# 4_324_039__3_3.net
KiCad netlist of a schematic drawn in Altium Designer
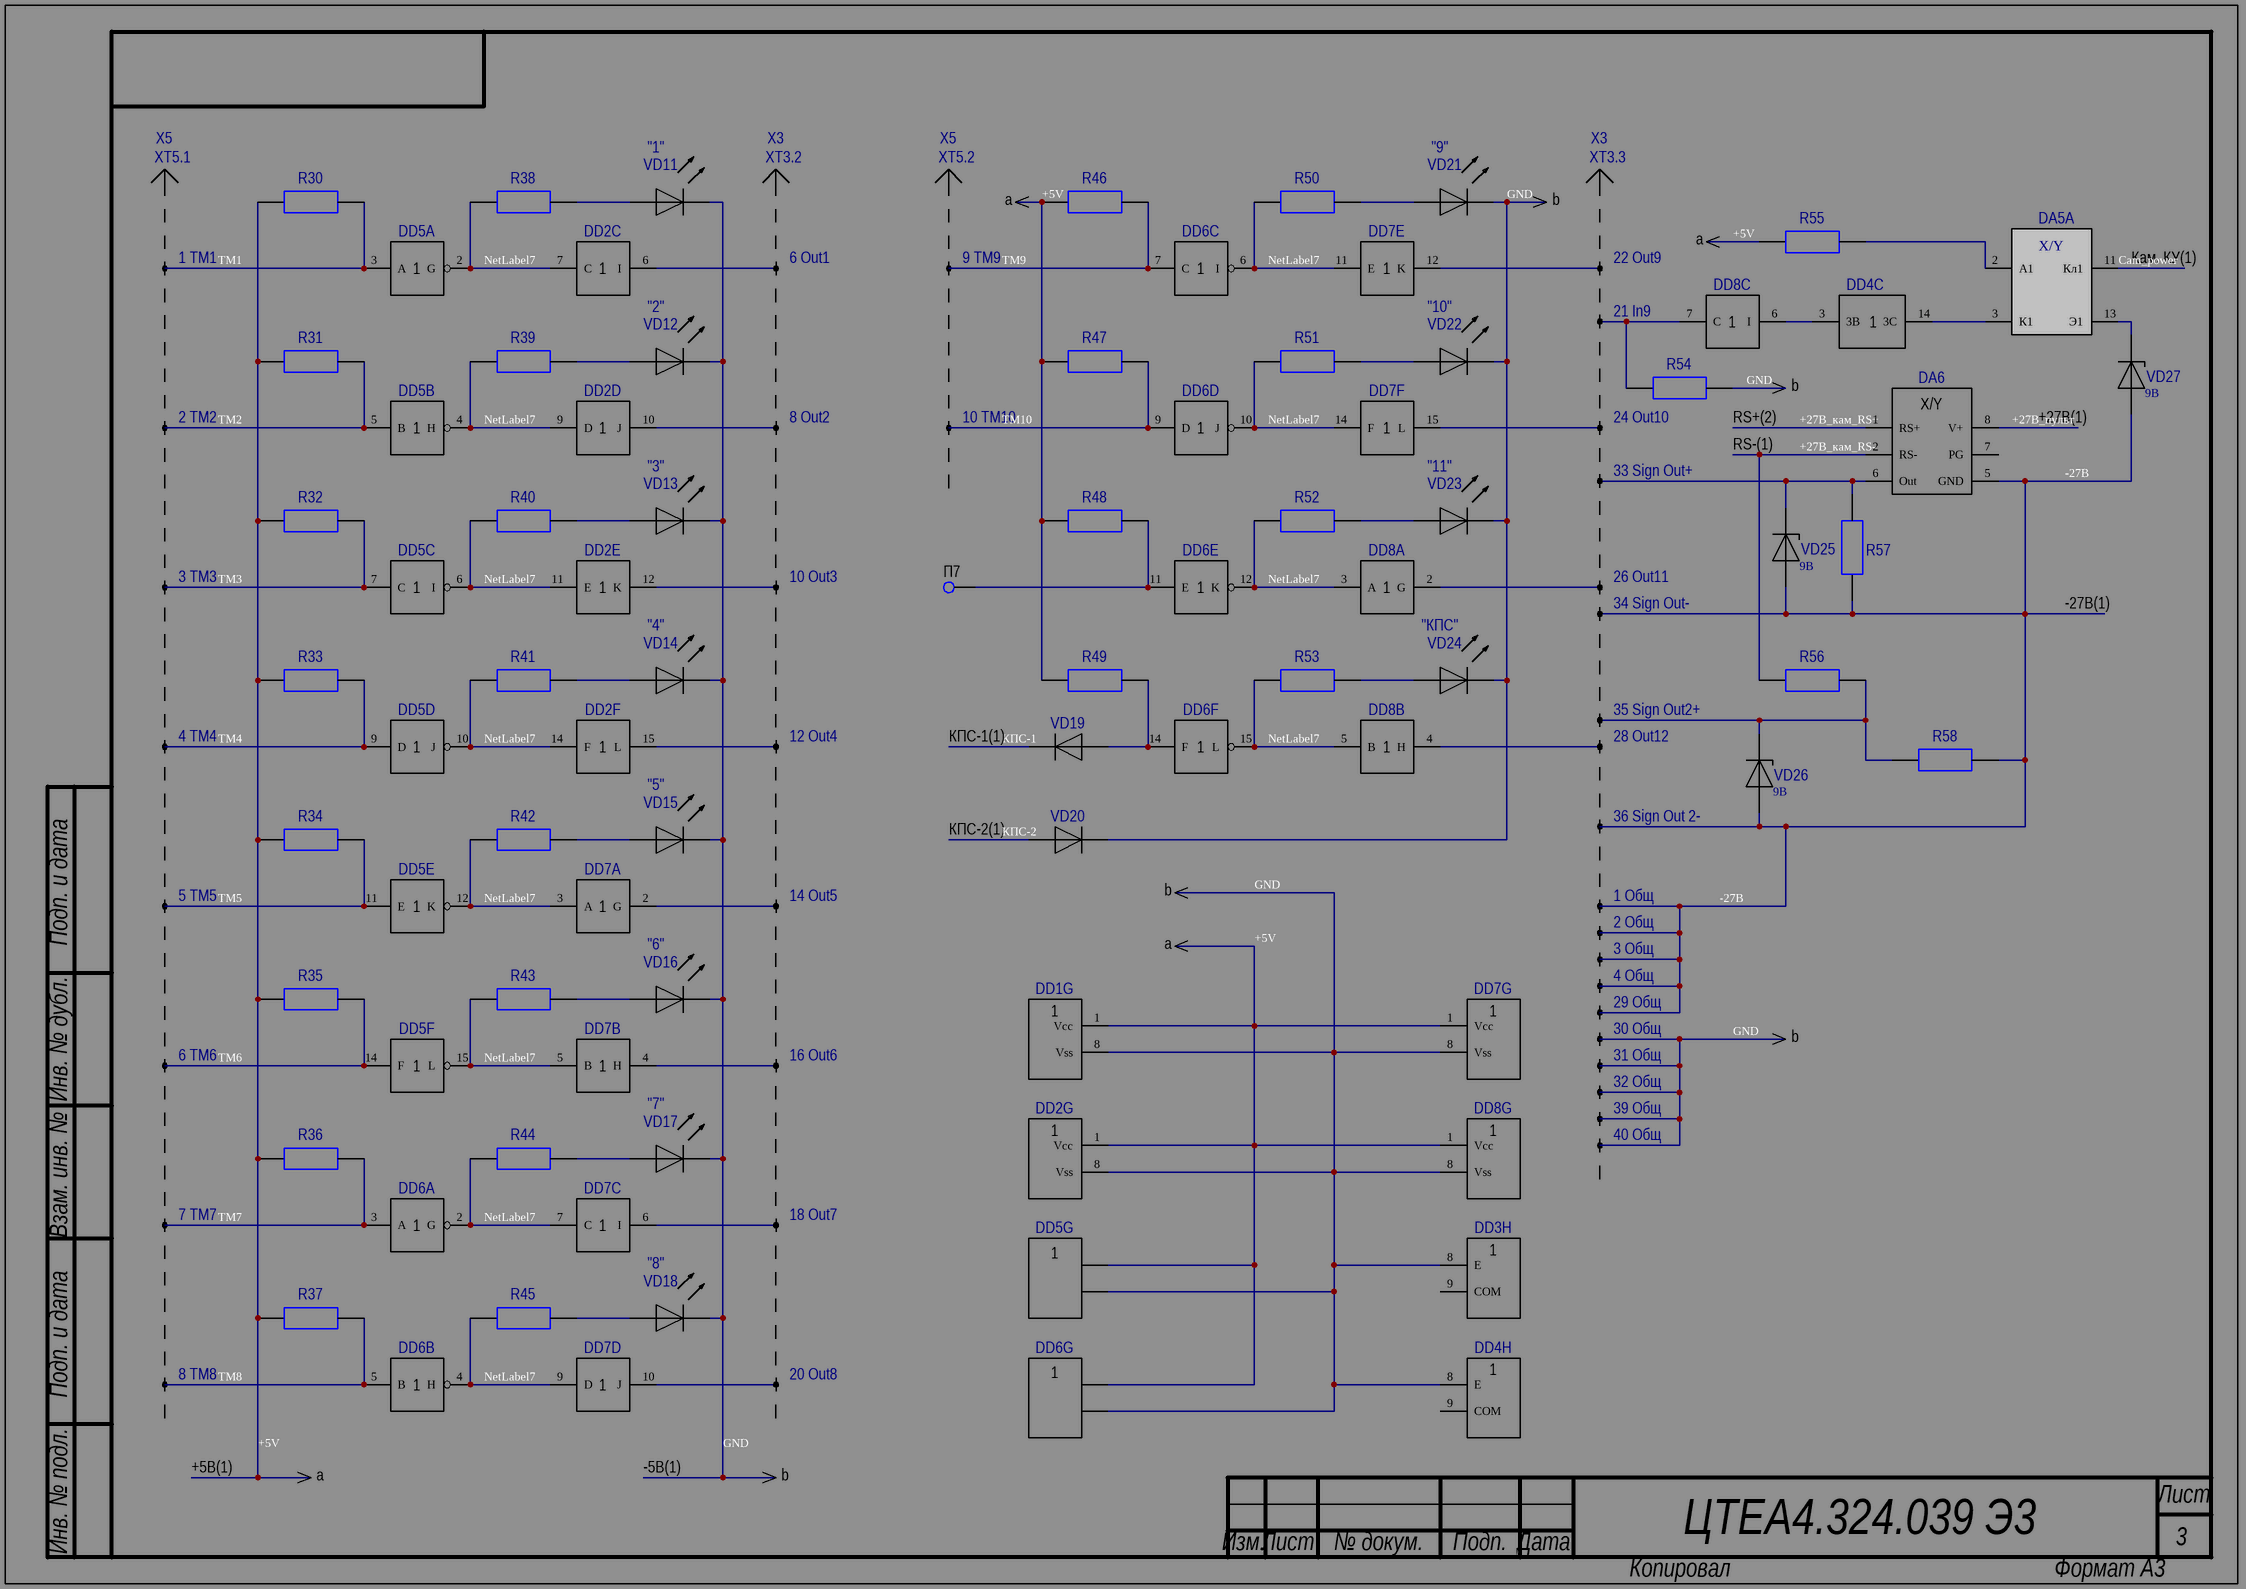
[diagram p0: ЦТЕА4.324.039_Э3_3.SchDoc]

(export (version "E")
  (design (tool "Eeschema 10.0.6"))
  (components
    (comp (ref "DA5")
      (value "249КП1С")
      (footprint "249KP1S_44_3208_125_12-3kl:249KP1S-44_3208_125_12")
      (libsource (lib "249KP1S_44_3208_125_12-3kl") (part "Microshema"))
    )
    (comp (ref "DA6")
      (value "MAX4172")
      (footprint "MAX4172")
      (libsource (lib "MAX4172-3kl") (part "MAX4172"))
    )
    (comp (ref "DD1")
      (value "Mikroshema")
      (footprint "CD4050BD")
      (description "CD4050BD")
      (libsource (lib "CD4050BD-3kl") (part "Mikroshema"))
    )
    (comp (ref "DD2")
      (value "Mikroshema")
      (footprint "CD4050BD")
      (description "CD4050BD")
      (libsource (lib "CD4050BD-3kl") (part "Mikroshema"))
    )
    (comp (ref "DD3")
      (value "Mikroshema")
      (footprint "UL2004AD")
      (description "ULN2004")
      (libsource (lib "ULN2004AD-3kl") (part "Mikroshema"))
    )
    (comp (ref "DD4")
      (value "Mikroshema")
      (footprint "UL2004AD")
      (description "ULN2004")
      (libsource (lib "ULN2004AD-3kl") (part "Mikroshema"))
    )
    (comp (ref "DD5")
      (value "Mikroshema")
      (footprint "CD4049UBD")
      (libsource (lib "CD4049UBD-3kl") (part "Mikroshema"))
    )
    (comp (ref "DD6")
      (value "Mikroshema")
      (footprint "CD4049UBD")
      (libsource (lib "CD4049UBD-3kl") (part "Mikroshema"))
    )
    (comp (ref "DD7")
      (value "Mikroshema")
      (footprint "CD4050BD")
      (description "CD4050BD")
      (libsource (lib "CD4050BD-3kl") (part "Mikroshema"))
    )
    (comp (ref "DD8")
      (value "Mikroshema")
      (footprint "CD4050BD")
      (description "CD4050BD")
      (libsource (lib "CD4050BD-3kl") (part "Mikroshema"))
    )
    (comp (ref "R30")
      (value "Res")
      (footprint "CR1206-JW-3301ELF")
      (libsource (lib "CR1206-JW-3301ELF-3kl") (part "Rezistor"))
    )
    (comp (ref "R31")
      (value "Res")
      (footprint "CR1206-JW-3301ELF")
      (libsource (lib "CR1206-JW-3301ELF-3kl") (part "Rezistor"))
    )
    (comp (ref "R32")
      (value "Res")
      (footprint "CR1206-JW-3301ELF")
      (libsource (lib "CR1206-JW-3301ELF-3kl") (part "Rezistor"))
    )
    (comp (ref "R33")
      (value "Res")
      (footprint "CR1206-JW-3301ELF")
      (libsource (lib "CR1206-JW-3301ELF-3kl") (part "Rezistor"))
    )
    (comp (ref "R34")
      (value "Res")
      (footprint "CR1206-JW-3301ELF")
      (libsource (lib "CR1206-JW-3301ELF-3kl") (part "Rezistor"))
    )
    (comp (ref "R35")
      (value "Res")
      (footprint "CR1206-JW-3301ELF")
      (libsource (lib "CR1206-JW-3301ELF-3kl") (part "Rezistor"))
    )
    (comp (ref "R36")
      (value "Res")
      (footprint "CR1206-JW-3301ELF")
      (libsource (lib "CR1206-JW-3301ELF-3kl") (part "Rezistor"))
    )
    (comp (ref "R37")
      (value "Res")
      (footprint "CR1206-JW-3301ELF")
      (libsource (lib "CR1206-JW-3301ELF-3kl") (part "Rezistor"))
    )
    (comp (ref "R38")
      (value "Res")
      (footprint "CR1206-JW-4700ELF")
      (libsource (lib "CR1206-JW-4700ELF-3kl") (part "Rezistor"))
    )
    (comp (ref "R39")
      (value "Res")
      (footprint "CR1206-JW-4700ELF")
      (libsource (lib "CR1206-JW-4700ELF-3kl") (part "Rezistor"))
    )
    (comp (ref "R40")
      (value "Res")
      (footprint "CR1206-JW-4700ELF")
      (libsource (lib "CR1206-JW-4700ELF-3kl") (part "Rezistor"))
    )
    (comp (ref "R41")
      (value "Res")
      (footprint "CR1206-JW-4700ELF")
      (libsource (lib "CR1206-JW-4700ELF-3kl") (part "Rezistor"))
    )
    (comp (ref "R42")
      (value "Res")
      (footprint "CR1206-JW-4700ELF")
      (libsource (lib "CR1206-JW-4700ELF-3kl") (part "Rezistor"))
    )
    (comp (ref "R43")
      (value "Res")
      (footprint "CR1206-JW-4700ELF")
      (libsource (lib "CR1206-JW-4700ELF-3kl") (part "Rezistor"))
    )
    (comp (ref "R44")
      (value "Res")
      (footprint "CR1206-JW-4700ELF")
      (libsource (lib "CR1206-JW-4700ELF-3kl") (part "Rezistor"))
    )
    (comp (ref "R45")
      (value "Res")
      (footprint "CR1206-JW-4700ELF")
      (libsource (lib "CR1206-JW-4700ELF-3kl") (part "Rezistor"))
    )
    (comp (ref "R46")
      (value "Res")
      (footprint "CR1206-JW-3301ELF")
      (libsource (lib "CR1206-JW-3301ELF-3kl") (part "Rezistor"))
    )
    (comp (ref "R47")
      (value "Res")
      (footprint "CR1206-JW-3301ELF")
      (libsource (lib "CR1206-JW-3301ELF-3kl") (part "Rezistor"))
    )
    (comp (ref "R48")
      (value "Res")
      (footprint "CR1206-JW-3301ELF")
      (libsource (lib "CR1206-JW-3301ELF-3kl") (part "Rezistor"))
    )
    (comp (ref "R49")
      (value "Res")
      (footprint "CR1206-JW-3301ELF")
      (libsource (lib "CR1206-JW-3301ELF-3kl") (part "Rezistor"))
    )
    (comp (ref "R50")
      (value "Res")
      (footprint "CR1206-JW-4700ELF")
      (libsource (lib "CR1206-JW-4700ELF-3kl") (part "Rezistor"))
    )
    (comp (ref "R51")
      (value "Res")
      (footprint "CR1206-JW-4700ELF")
      (libsource (lib "CR1206-JW-4700ELF-3kl") (part "Rezistor"))
    )
    (comp (ref "R52")
      (value "Res")
      (footprint "CR1206-JW-4700ELF")
      (libsource (lib "CR1206-JW-4700ELF-3kl") (part "Rezistor"))
    )
    (comp (ref "R53")
      (value "Res")
      (footprint "CR1206-JW-4700ELF")
      (libsource (lib "CR1206-JW-4700ELF-3kl") (part "Rezistor"))
    )
    (comp (ref "R54")
      (value "Res")
      (footprint "CR1206-JW-4701ELF")
      (libsource (lib "CR1206-JW-4701ELF-3kl") (part "Rezistor"))
    )
    (comp (ref "R55")
      (value "Res")
      (footprint "CR1206-JW-3300ELF")
      (libsource (lib "CR1206-JW-3300ELF-3kl") (part "Rezistor"))
    )
    (comp (ref "R56")
      (value "Res")
      (footprint "CR1206-JW-4701ELF")
      (libsource (lib "CR1206-JW-4701ELF-3kl") (part "Rezistor"))
    )
    (comp (ref "R57")
      (value "Res")
      (footprint "CR1206-JW-1001ELF")
      (libsource (lib "CR1206-JW-1001ELF-3kl") (part "Rezistor"))
    )
    (comp (ref "R58")
      (value "Res")
      (footprint "CR1206-JW-4700ELF")
      (libsource (lib "CR1206-JW-4700ELF-3kl") (part "Rezistor"))
    )
    (comp (ref "VD11")
      (value "\"1\"")
      (footprint "HLMP-D150")
      (libsource (lib "HLMP-D150-3kl") (part "Svetodiod"))
    )
    (comp (ref "VD12")
      (value "\"2\"")
      (footprint "HLMP-D150")
      (libsource (lib "HLMP-D150-3kl") (part "Svetodiod"))
    )
    (comp (ref "VD13")
      (value "\"3\"")
      (footprint "HLMP-D150")
      (libsource (lib "HLMP-D150-3kl") (part "Svetodiod"))
    )
    (comp (ref "VD14")
      (value "\"4\"")
      (footprint "HLMP-D150")
      (libsource (lib "HLMP-D150-3kl") (part "Svetodiod"))
    )
    (comp (ref "VD15")
      (value "\"5\"")
      (footprint "HLMP-D150")
      (libsource (lib "HLMP-D150-3kl") (part "Svetodiod"))
    )
    (comp (ref "VD16")
      (value "\"6\"")
      (footprint "HLMP-D150")
      (libsource (lib "HLMP-D150-3kl") (part "Svetodiod"))
    )
    (comp (ref "VD17")
      (value "\"7\"")
      (footprint "HLMP-D150")
      (libsource (lib "HLMP-D150-3kl") (part "Svetodiod"))
    )
    (comp (ref "VD18")
      (value "\"8\"")
      (footprint "HLMP-D150")
      (libsource (lib "HLMP-D150-3kl") (part "Svetodiod"))
    )
    (comp (ref "VD19")
      (value "Schottky")
      (footprint "10MQ060N")
      (libsource (lib "10MQ060N-3kl") (part "Diod"))
    )
    (comp (ref "VD20")
      (value "Schottky")
      (footprint "10MQ060N")
      (libsource (lib "10MQ060N-3kl") (part "Diod"))
    )
    (comp (ref "VD21")
      (value "\"9\"")
      (footprint "HLMP-D150")
      (libsource (lib "HLMP-D150-3kl") (part "Svetodiod"))
    )
    (comp (ref "VD22")
      (value "\"10\"")
      (footprint "HLMP-D150")
      (libsource (lib "HLMP-D150-3kl") (part "Svetodiod"))
    )
    (comp (ref "VD23")
      (value "\"11\"")
      (footprint "HLMP-D150")
      (libsource (lib "HLMP-D150-3kl") (part "Svetodiod"))
    )
    (comp (ref "VD24")
      (value "\"КПС\"")
      (footprint "HLMP-D150")
      (libsource (lib "HLMP-D150-3kl") (part "Svetodiod"))
    )
    (comp (ref "VD25")
      (value "9В")
      (footprint "1N4754A-25_0000_145_18")
      (description "zener")
      (libsource (lib "1N4754A-f1-3kl") (part "Diod"))
    )
    (comp (ref "VD26")
      (value "9В")
      (footprint "1N4754A-25_0000_145_18")
      (description "zener")
      (libsource (lib "1N4754A-f1-3kl") (part "Diod"))
    )
    (comp (ref "VD27")
      (value "9В")
      (footprint "1N4754A-25_0000_145_18")
      (description "zener")
      (libsource (lib "1N4754A-f1-3kl") (part "Diod"))
    )
    (comp (ref "XT3")
      (value "1 Общ")
      (footprint "PLD-40")
      (libsource (lib "PLD-40-3kl") (part "Razem shtyrevoj"))
    )
    (comp (ref "XT5")
      (value "1 ТМ1")
      (footprint "PLD-16")
      (description "PLD16")
      (libsource (lib "PLD-16-3kl") (part "Razem shtyrevoj"))
    )
    (comp (ref "П7")
      (value "~")
      (footprint "Pad")
      (description "pad")
      (libsource (lib "Pad-3kl") (part "Pad"))
    )
  )
  (nets
    (net (code "1") (name "/+5V") (class "Default")
      (node (ref "DD1") (pin "1") (pinfunction "Vcc_1") (pintype "power_in"))
      (node (ref "DD2") (pin "1") (pinfunction "Vcc_1") (pintype "power_in"))
      (node (ref "DD5") (pin "1") (pinfunction "Vcc_1") (pintype "power_in"))
      (node (ref "DD6") (pin "1") (pinfunction "Vcc_1") (pintype "power_in"))
      (node (ref "DD7") (pin "1") (pinfunction "Vcc_1") (pintype "power_in"))
      (node (ref "DD8") (pin "1") (pinfunction "Vcc_1") (pintype "power_in"))
      (node (ref "R30") (pin "1") (pinfunction "1_1") (pintype "passive"))
      (node (ref "R31") (pin "1") (pinfunction "1_1") (pintype "passive"))
      (node (ref "R32") (pin "1") (pinfunction "1_1") (pintype "passive"))
      (node (ref "R33") (pin "1") (pinfunction "1_1") (pintype "passive"))
      (node (ref "R34") (pin "1") (pinfunction "1_1") (pintype "passive"))
      (node (ref "R35") (pin "1") (pinfunction "1_1") (pintype "passive"))
      (node (ref "R36") (pin "1") (pinfunction "1_1") (pintype "passive"))
      (node (ref "R37") (pin "1") (pinfunction "1_1") (pintype "passive"))
      (node (ref "R46") (pin "1") (pinfunction "1_1") (pintype "passive"))
      (node (ref "R47") (pin "1") (pinfunction "1_1") (pintype "passive"))
      (node (ref "R48") (pin "1") (pinfunction "1_1") (pintype "passive"))
      (node (ref "R49") (pin "1") (pinfunction "1_1") (pintype "passive"))
      (node (ref "R55") (pin "1") (pinfunction "1_1") (pintype "passive"))
    )
    (net (code "2") (name "/+27В_кам_RS+") (class "Default")
      (node (ref "DA6") (pin "1") (pinfunction "RS+_1") (pintype "passive"))
    )
    (net (code "3") (name "/+27В_кам_RS-") (class "Default")
      (node (ref "DA6") (pin "2") (pinfunction "RS-_2") (pintype "passive"))
      (node (ref "R56") (pin "1") (pinfunction "1_1") (pintype "passive"))
    )
    (net (code "4") (name "/+27В_пульт") (class "Default")
      (node (ref "DA6") (pin "8") (pinfunction "V+_8") (pintype "passive"))
    )
    (net (code "5") (name "/-27В") (class "Default")
      (node (ref "DA6") (pin "5") (pinfunction "GND_5") (pintype "passive"))
      (node (ref "R57") (pin "1") (pinfunction "1_1") (pintype "passive"))
      (node (ref "R58") (pin "2") (pinfunction "2_2") (pintype "passive"))
      (node (ref "VD25") (pin "1") (pinfunction "A_1") (pintype "passive"))
      (node (ref "VD26") (pin "1") (pinfunction "A_1") (pintype "passive"))
      (node (ref "VD27") (pin "1") (pinfunction "A_1") (pintype "passive"))
      (node (ref "XT3") (pin "1") (pinfunction "1_1") (pintype "passive"))
      (node (ref "XT3") (pin "2") (pinfunction "2_2") (pintype "passive"))
      (node (ref "XT3") (pin "29") (pinfunction "29_29") (pintype "passive"))
      (node (ref "XT3") (pin "3") (pinfunction "3_3") (pintype "passive"))
      (node (ref "XT3") (pin "34") (pinfunction "34_34") (pintype "passive"))
      (node (ref "XT3") (pin "36") (pinfunction "36_36") (pintype "passive"))
      (node (ref "XT3") (pin "4") (pinfunction "4_4") (pintype "passive"))
    )
    (net (code "6") (name "/Cam_power") (class "Default")
      (node (ref "DA5") (pin "11") (pinfunction "Кл1_11") (pintype "passive"))
    )
    (net (code "7") (name "/GND") (class "Default")
      (node (ref "DD1") (pin "8") (pinfunction "Vss_8") (pintype "power_in"))
      (node (ref "DD2") (pin "8") (pinfunction "Vss_8") (pintype "power_in"))
      (node (ref "DD3") (pin "8") (pinfunction "E_8") (pintype "power_in"))
      (node (ref "DD4") (pin "8") (pinfunction "E_8") (pintype "power_in"))
      (node (ref "DD5") (pin "8") (pinfunction "Vss_8") (pintype "power_in"))
      (node (ref "DD6") (pin "8") (pinfunction "Vss_8") (pintype "power_in"))
      (node (ref "DD7") (pin "8") (pinfunction "Vss_8") (pintype "power_in"))
      (node (ref "DD8") (pin "8") (pinfunction "Vss_8") (pintype "power_in"))
      (node (ref "R54") (pin "2") (pinfunction "2_2") (pintype "passive"))
      (node (ref "VD11") (pin "2") (pinfunction "C_2") (pintype "passive"))
      (node (ref "VD12") (pin "2") (pinfunction "C_2") (pintype "passive"))
      (node (ref "VD13") (pin "2") (pinfunction "C_2") (pintype "passive"))
      (node (ref "VD14") (pin "2") (pinfunction "C_2") (pintype "passive"))
      (node (ref "VD15") (pin "2") (pinfunction "C_2") (pintype "passive"))
      (node (ref "VD16") (pin "2") (pinfunction "C_2") (pintype "passive"))
      (node (ref "VD17") (pin "2") (pinfunction "C_2") (pintype "passive"))
      (node (ref "VD18") (pin "2") (pinfunction "C_2") (pintype "passive"))
      (node (ref "VD20") (pin "2") (pinfunction "C_2") (pintype "passive"))
      (node (ref "VD21") (pin "2") (pinfunction "C_2") (pintype "passive"))
      (node (ref "VD22") (pin "2") (pinfunction "C_2") (pintype "passive"))
      (node (ref "VD23") (pin "2") (pinfunction "C_2") (pintype "passive"))
      (node (ref "VD24") (pin "2") (pinfunction "C_2") (pintype "passive"))
      (node (ref "XT3") (pin "30") (pinfunction "30_30") (pintype "passive"))
      (node (ref "XT3") (pin "31") (pinfunction "31_31") (pintype "passive"))
      (node (ref "XT3") (pin "32") (pinfunction "32_32") (pintype "passive"))
      (node (ref "XT3") (pin "39") (pinfunction "39_39") (pintype "passive"))
      (node (ref "XT3") (pin "40") (pinfunction "40_40") (pintype "passive"))
    )
    (net (code "8") (name "/NetLabel7") (class "Default")
      (node (ref "DD2") (pin "11") (pinfunction "E_11") (pintype "passive"))
      (node (ref "DD2") (pin "14") (pinfunction "F_14") (pintype "passive"))
      (node (ref "DD2") (pin "7") (pinfunction "C_7") (pintype "passive"))
      (node (ref "DD2") (pin "9") (pinfunction "D_9") (pintype "passive"))
      (node (ref "DD5") (pin "10") (pinfunction "J_10") (pintype "passive"))
      (node (ref "DD5") (pin "12") (pinfunction "K_12") (pintype "passive"))
      (node (ref "DD5") (pin "15") (pinfunction "L_15") (pintype "passive"))
      (node (ref "DD5") (pin "2") (pinfunction "G_2") (pintype "passive"))
      (node (ref "DD5") (pin "4") (pinfunction "H_4") (pintype "passive"))
      (node (ref "DD5") (pin "6") (pinfunction "I_6") (pintype "passive"))
      (node (ref "DD6") (pin "10") (pinfunction "J_10") (pintype "passive"))
      (node (ref "DD6") (pin "12") (pinfunction "K_12") (pintype "passive"))
      (node (ref "DD6") (pin "15") (pinfunction "L_15") (pintype "passive"))
      (node (ref "DD6") (pin "2") (pinfunction "G_2") (pintype "passive"))
      (node (ref "DD6") (pin "4") (pinfunction "H_4") (pintype "passive"))
      (node (ref "DD6") (pin "6") (pinfunction "I_6") (pintype "passive"))
      (node (ref "DD7") (pin "11") (pinfunction "E_11") (pintype "passive"))
      (node (ref "DD7") (pin "14") (pinfunction "F_14") (pintype "passive"))
      (node (ref "DD7") (pin "3") (pinfunction "A_3") (pintype "passive"))
      (node (ref "DD7") (pin "5") (pinfunction "B_5") (pintype "passive"))
      (node (ref "DD7") (pin "7") (pinfunction "C_7") (pintype "passive"))
      (node (ref "DD7") (pin "9") (pinfunction "D_9") (pintype "passive"))
      (node (ref "DD8") (pin "3") (pinfunction "A_3") (pintype "passive"))
      (node (ref "DD8") (pin "5") (pinfunction "B_5") (pintype "passive"))
      (node (ref "R38") (pin "1") (pinfunction "1_1") (pintype "passive"))
      (node (ref "R39") (pin "1") (pinfunction "1_1") (pintype "passive"))
      (node (ref "R40") (pin "1") (pinfunction "1_1") (pintype "passive"))
      (node (ref "R41") (pin "1") (pinfunction "1_1") (pintype "passive"))
      (node (ref "R42") (pin "1") (pinfunction "1_1") (pintype "passive"))
      (node (ref "R43") (pin "1") (pinfunction "1_1") (pintype "passive"))
      (node (ref "R44") (pin "1") (pinfunction "1_1") (pintype "passive"))
      (node (ref "R45") (pin "1") (pinfunction "1_1") (pintype "passive"))
      (node (ref "R50") (pin "1") (pinfunction "1_1") (pintype "passive"))
      (node (ref "R51") (pin "1") (pinfunction "1_1") (pintype "passive"))
      (node (ref "R52") (pin "1") (pinfunction "1_1") (pintype "passive"))
      (node (ref "R53") (pin "1") (pinfunction "1_1") (pintype "passive"))
    )
    (net (code "9") (name "/КПС-1") (class "Default")
      (node (ref "VD19") (pin "2") (pinfunction "C_2") (pintype "passive"))
    )
    (net (code "10") (name "/КПС-2") (class "Default")
      (node (ref "VD20") (pin "1") (pinfunction "A_1") (pintype "passive"))
    )
    (net (code "11") (name "/ТМ1") (class "Default")
      (node (ref "DD5") (pin "3") (pinfunction "A_3") (pintype "passive"))
      (node (ref "R30") (pin "2") (pinfunction "2_2") (pintype "passive"))
      (node (ref "XT5") (pin "1") (pinfunction "1_1") (pintype "passive"))
    )
    (net (code "12") (name "/ТМ2") (class "Default")
      (node (ref "DD5") (pin "5") (pinfunction "B_5") (pintype "passive"))
      (node (ref "R31") (pin "2") (pinfunction "2_2") (pintype "passive"))
      (node (ref "XT5") (pin "2") (pinfunction "2_2") (pintype "passive"))
    )
    (net (code "13") (name "/ТМ3") (class "Default")
      (node (ref "DD5") (pin "7") (pinfunction "C_7") (pintype "passive"))
      (node (ref "R32") (pin "2") (pinfunction "2_2") (pintype "passive"))
      (node (ref "XT5") (pin "3") (pinfunction "3_3") (pintype "passive"))
    )
    (net (code "14") (name "/ТМ4") (class "Default")
      (node (ref "DD5") (pin "9") (pinfunction "D_9") (pintype "passive"))
      (node (ref "R33") (pin "2") (pinfunction "2_2") (pintype "passive"))
      (node (ref "XT5") (pin "4") (pinfunction "4_4") (pintype "passive"))
    )
    (net (code "15") (name "/ТМ5") (class "Default")
      (node (ref "DD5") (pin "11") (pinfunction "E_11") (pintype "passive"))
      (node (ref "R34") (pin "2") (pinfunction "2_2") (pintype "passive"))
      (node (ref "XT5") (pin "5") (pinfunction "5_5") (pintype "passive"))
    )
    (net (code "16") (name "/ТМ6") (class "Default")
      (node (ref "DD5") (pin "14") (pinfunction "F_14") (pintype "passive"))
      (node (ref "R35") (pin "2") (pinfunction "2_2") (pintype "passive"))
      (node (ref "XT5") (pin "6") (pinfunction "6_6") (pintype "passive"))
    )
    (net (code "17") (name "/ТМ7") (class "Default")
      (node (ref "DD6") (pin "3") (pinfunction "A_3") (pintype "passive"))
      (node (ref "R36") (pin "2") (pinfunction "2_2") (pintype "passive"))
      (node (ref "XT5") (pin "7") (pinfunction "7_7") (pintype "passive"))
    )
    (net (code "18") (name "/ТМ8") (class "Default")
      (node (ref "DD6") (pin "5") (pinfunction "B_5") (pintype "passive"))
      (node (ref "R37") (pin "2") (pinfunction "2_2") (pintype "passive"))
      (node (ref "XT5") (pin "8") (pinfunction "8_8") (pintype "passive"))
    )
    (net (code "19") (name "/ТМ9") (class "Default")
      (node (ref "DD6") (pin "7") (pinfunction "C_7") (pintype "passive"))
      (node (ref "R46") (pin "2") (pinfunction "2_2") (pintype "passive"))
      (node (ref "XT5") (pin "9") (pinfunction "9_9") (pintype "passive"))
    )
    (net (code "20") (name "/ТМ10") (class "Default")
      (node (ref "DD6") (pin "9") (pinfunction "D_9") (pintype "passive"))
      (node (ref "R47") (pin "2") (pinfunction "2_2") (pintype "passive"))
      (node (ref "XT5") (pin "10") (pinfunction "10_10") (pintype "passive"))
    )
    (net (code "21") (name "Net-(DA5A-А1)") (class "Default")
      (node (ref "DA5") (pin "2") (pinfunction "А1_2") (pintype "passive"))
      (node (ref "R55") (pin "2") (pinfunction "2_2") (pintype "passive"))
    )
    (net (code "22") (name "Net-(DA5A-К1)") (class "Default")
      (node (ref "DA5") (pin "3") (pinfunction "К1_3") (pintype "passive"))
      (node (ref "DD4") (pin "14") (pinfunction "3C_14") (pintype "passive"))
    )
    (net (code "23") (name "Net-(DA5A-Э1)") (class "Default")
      (node (ref "DA5") (pin "13") (pinfunction "Э1_13") (pintype "passive"))
      (node (ref "VD27") (pin "2") (pinfunction "C_2") (pintype "passive"))
    )
    (net (code "24") (name "Net-(DA6-Out)") (class "Default")
      (node (ref "DA6") (pin "6") (pinfunction "Out_6") (pintype "passive"))
      (node (ref "R57") (pin "2") (pinfunction "2_2") (pintype "passive"))
      (node (ref "VD25") (pin "2") (pinfunction "C_2") (pintype "passive"))
      (node (ref "XT3") (pin "33") (pinfunction "33_33") (pintype "passive"))
    )
    (net (code "25") (name "Net-(DD2C-I)") (class "Default")
      (node (ref "DD2") (pin "6") (pinfunction "I_6") (pintype "passive"))
      (node (ref "XT3") (pin "6") (pinfunction "6_6") (pintype "passive"))
    )
    (net (code "26") (name "Net-(DD2D-J)") (class "Default")
      (node (ref "DD2") (pin "10") (pinfunction "J_10") (pintype "passive"))
      (node (ref "XT3") (pin "8") (pinfunction "8_8") (pintype "passive"))
    )
    (net (code "27") (name "Net-(DD2E-K)") (class "Default")
      (node (ref "DD2") (pin "12") (pinfunction "K_12") (pintype "passive"))
      (node (ref "XT3") (pin "10") (pinfunction "10_10") (pintype "passive"))
    )
    (net (code "28") (name "Net-(DD2F-L)") (class "Default")
      (node (ref "DD2") (pin "15") (pinfunction "L_15") (pintype "passive"))
      (node (ref "XT3") (pin "12") (pinfunction "12_12") (pintype "passive"))
    )
    (net (code "29") (name "Net-(DD4C-3B)") (class "Default")
      (node (ref "DD4") (pin "3") (pinfunction "3B_3") (pintype "passive"))
      (node (ref "DD8") (pin "6") (pinfunction "I_6") (pintype "passive"))
    )
    (net (code "30") (name "Net-(DD6E-E)") (class "Default")
      (node (ref "DD6") (pin "11") (pinfunction "E_11") (pintype "passive"))
      (node (ref "R48") (pin "2") (pinfunction "2_2") (pintype "passive"))
      (node (ref "П7") (pin "1") (pinfunction "1_1") (pintype "passive"))
    )
    (net (code "31") (name "Net-(DD6F-F)") (class "Default")
      (node (ref "DD6") (pin "14") (pinfunction "F_14") (pintype "passive"))
      (node (ref "R49") (pin "2") (pinfunction "2_2") (pintype "passive"))
      (node (ref "VD19") (pin "1") (pinfunction "A_1") (pintype "passive"))
    )
    (net (code "32") (name "Net-(DD7A-G)") (class "Default")
      (node (ref "DD7") (pin "2") (pinfunction "G_2") (pintype "passive"))
      (node (ref "XT3") (pin "14") (pinfunction "14_14") (pintype "passive"))
    )
    (net (code "33") (name "Net-(DD7B-H)") (class "Default")
      (node (ref "DD7") (pin "4") (pinfunction "H_4") (pintype "passive"))
      (node (ref "XT3") (pin "16") (pinfunction "16_16") (pintype "passive"))
    )
    (net (code "34") (name "Net-(DD7C-I)") (class "Default")
      (node (ref "DD7") (pin "6") (pinfunction "I_6") (pintype "passive"))
      (node (ref "XT3") (pin "18") (pinfunction "18_18") (pintype "passive"))
    )
    (net (code "35") (name "Net-(DD7D-J)") (class "Default")
      (node (ref "DD7") (pin "10") (pinfunction "J_10") (pintype "passive"))
      (node (ref "XT3") (pin "20") (pinfunction "20_20") (pintype "passive"))
    )
    (net (code "36") (name "Net-(DD7E-K)") (class "Default")
      (node (ref "DD7") (pin "12") (pinfunction "K_12") (pintype "passive"))
      (node (ref "XT3") (pin "22") (pinfunction "22_22") (pintype "passive"))
    )
    (net (code "37") (name "Net-(DD7F-L)") (class "Default")
      (node (ref "DD7") (pin "15") (pinfunction "L_15") (pintype "passive"))
      (node (ref "XT3") (pin "24") (pinfunction "24_24") (pintype "passive"))
    )
    (net (code "38") (name "Net-(DD8A-G)") (class "Default")
      (node (ref "DD8") (pin "2") (pinfunction "G_2") (pintype "passive"))
      (node (ref "XT3") (pin "26") (pinfunction "26_26") (pintype "passive"))
    )
    (net (code "39") (name "Net-(DD8B-H)") (class "Default")
      (node (ref "DD8") (pin "4") (pinfunction "H_4") (pintype "passive"))
      (node (ref "XT3") (pin "28") (pinfunction "28_28") (pintype "passive"))
    )
    (net (code "40") (name "Net-(DD8C-C)") (class "Default")
      (node (ref "DD8") (pin "7") (pinfunction "C_7") (pintype "passive"))
      (node (ref "R54") (pin "1") (pinfunction "1_1") (pintype "passive"))
      (node (ref "XT3") (pin "21") (pinfunction "21_21") (pintype "passive"))
    )
    (net (code "41") (name "Net-(VD11-A)") (class "Default")
      (node (ref "R38") (pin "2") (pinfunction "2_2") (pintype "passive"))
      (node (ref "VD11") (pin "1") (pinfunction "A_1") (pintype "passive"))
    )
    (net (code "42") (name "Net-(VD12-A)") (class "Default")
      (node (ref "R39") (pin "2") (pinfunction "2_2") (pintype "passive"))
      (node (ref "VD12") (pin "1") (pinfunction "A_1") (pintype "passive"))
    )
    (net (code "43") (name "Net-(VD13-A)") (class "Default")
      (node (ref "R40") (pin "2") (pinfunction "2_2") (pintype "passive"))
      (node (ref "VD13") (pin "1") (pinfunction "A_1") (pintype "passive"))
    )
    (net (code "44") (name "Net-(VD14-A)") (class "Default")
      (node (ref "R41") (pin "2") (pinfunction "2_2") (pintype "passive"))
      (node (ref "VD14") (pin "1") (pinfunction "A_1") (pintype "passive"))
    )
    (net (code "45") (name "Net-(VD15-A)") (class "Default")
      (node (ref "R42") (pin "2") (pinfunction "2_2") (pintype "passive"))
      (node (ref "VD15") (pin "1") (pinfunction "A_1") (pintype "passive"))
    )
    (net (code "46") (name "Net-(VD16-A)") (class "Default")
      (node (ref "R43") (pin "2") (pinfunction "2_2") (pintype "passive"))
      (node (ref "VD16") (pin "1") (pinfunction "A_1") (pintype "passive"))
    )
    (net (code "47") (name "Net-(VD17-A)") (class "Default")
      (node (ref "R44") (pin "2") (pinfunction "2_2") (pintype "passive"))
      (node (ref "VD17") (pin "1") (pinfunction "A_1") (pintype "passive"))
    )
    (net (code "48") (name "Net-(VD18-A)") (class "Default")
      (node (ref "R45") (pin "2") (pinfunction "2_2") (pintype "passive"))
      (node (ref "VD18") (pin "1") (pinfunction "A_1") (pintype "passive"))
    )
    (net (code "49") (name "Net-(VD21-A)") (class "Default")
      (node (ref "R50") (pin "2") (pinfunction "2_2") (pintype "passive"))
      (node (ref "VD21") (pin "1") (pinfunction "A_1") (pintype "passive"))
    )
    (net (code "50") (name "Net-(VD22-A)") (class "Default")
      (node (ref "R51") (pin "2") (pinfunction "2_2") (pintype "passive"))
      (node (ref "VD22") (pin "1") (pinfunction "A_1") (pintype "passive"))
    )
    (net (code "51") (name "Net-(VD23-A)") (class "Default")
      (node (ref "R52") (pin "2") (pinfunction "2_2") (pintype "passive"))
      (node (ref "VD23") (pin "1") (pinfunction "A_1") (pintype "passive"))
    )
    (net (code "52") (name "Net-(VD24-A)") (class "Default")
      (node (ref "R53") (pin "2") (pinfunction "2_2") (pintype "passive"))
      (node (ref "VD24") (pin "1") (pinfunction "A_1") (pintype "passive"))
    )
    (net (code "53") (name "Net-(VD26-C)") (class "Default")
      (node (ref "R56") (pin "2") (pinfunction "2_2") (pintype "passive"))
      (node (ref "R58") (pin "1") (pinfunction "1_1") (pintype "passive"))
      (node (ref "VD26") (pin "2") (pinfunction "C_2") (pintype "passive"))
      (node (ref "XT3") (pin "35") (pinfunction "35_35") (pintype "passive"))
    )
    (net (code "54") (name "unconnected-(DA6-PG-Pad7)") (class "Default")
      (node (ref "DA6") (pin "7") (pinfunction "PG_7") (pintype "passive"))
    )
    (net (code "55") (name "unconnected-(DD3H-COM-Pad9)") (class "Default")
      (node (ref "DD3") (pin "9") (pinfunction "COM_9") (pintype "power_in"))
    )
    (net (code "56") (name "unconnected-(DD4H-COM-Pad9)") (class "Default")
      (node (ref "DD4") (pin "9") (pinfunction "COM_9") (pintype "power_in"))
    )
  )
)
